# Toplevel.net
KiCad netlist of a schematic drawn in Altium Designer
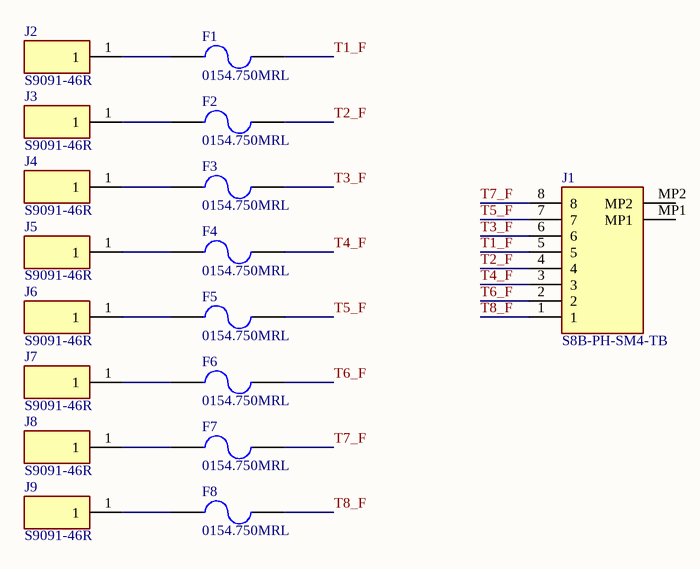
[diagram p0: Toplevel.SchDoc]

(export (version "E")
  (design (tool "Eeschema 10.0.6"))
  (components
    (comp (ref "F1")
      (value "0154.750MRL")
      (footprint "0451Series_LTF")
      (description "FUSE BOARD MNT 750MA 125VAC/VDC")
      (fields
        (field (name "MANUFACTURER") "Littelfuse Inc.")
        (field (name "DIGIKEY PART NUMBER") "F2576CT-ND")
      )
      (libsource (lib "ts_standard_library") (part "Fuse"))
    )
    (comp (ref "F2")
      (value "0154.750MRL")
      (footprint "0451Series_LTF")
      (description "FUSE BOARD MNT 750MA 125VAC/VDC")
      (fields
        (field (name "MANUFACTURER") "Littelfuse Inc.")
        (field (name "DIGIKEY PART NUMBER") "F2576CT-ND")
      )
      (libsource (lib "ts_standard_library") (part "Fuse"))
    )
    (comp (ref "F3")
      (value "0154.750MRL")
      (footprint "0451Series_LTF")
      (description "FUSE BOARD MNT 750MA 125VAC/VDC")
      (fields
        (field (name "MANUFACTURER") "Littelfuse Inc.")
        (field (name "DIGIKEY PART NUMBER") "F2576CT-ND")
      )
      (libsource (lib "ts_standard_library") (part "Fuse"))
    )
    (comp (ref "F4")
      (value "0154.750MRL")
      (footprint "0451Series_LTF")
      (description "FUSE BOARD MNT 750MA 125VAC/VDC")
      (fields
        (field (name "MANUFACTURER") "Littelfuse Inc.")
        (field (name "DIGIKEY PART NUMBER") "F2576CT-ND")
      )
      (libsource (lib "ts_standard_library") (part "Fuse"))
    )
    (comp (ref "F5")
      (value "0154.750MRL")
      (footprint "0451Series_LTF")
      (description "FUSE BOARD MNT 750MA 125VAC/VDC")
      (fields
        (field (name "MANUFACTURER") "Littelfuse Inc.")
        (field (name "DIGIKEY PART NUMBER") "F2576CT-ND")
      )
      (libsource (lib "ts_standard_library") (part "Fuse"))
    )
    (comp (ref "F6")
      (value "0154.750MRL")
      (footprint "0451Series_LTF")
      (description "FUSE BOARD MNT 750MA 125VAC/VDC")
      (fields
        (field (name "MANUFACTURER") "Littelfuse Inc.")
        (field (name "DIGIKEY PART NUMBER") "F2576CT-ND")
      )
      (libsource (lib "ts_standard_library") (part "Fuse"))
    )
    (comp (ref "F7")
      (value "0154.750MRL")
      (footprint "0451Series_LTF")
      (description "FUSE BOARD MNT 750MA 125VAC/VDC")
      (fields
        (field (name "MANUFACTURER") "Littelfuse Inc.")
        (field (name "DIGIKEY PART NUMBER") "F2576CT-ND")
      )
      (libsource (lib "ts_standard_library") (part "Fuse"))
    )
    (comp (ref "F8")
      (value "0154.750MRL")
      (footprint "0451Series_LTF")
      (description "FUSE BOARD MNT 750MA 125VAC/VDC")
      (fields
        (field (name "MANUFACTURER") "Littelfuse Inc.")
        (field (name "DIGIKEY PART NUMBER") "F2576CT-ND")
      )
      (libsource (lib "ts_standard_library") (part "Fuse"))
    )
    (comp (ref "J1")
      (value "S8B-PH-SM4-TB")
      (footprint "SamacSys:S8BPHSM4TB")
      (description "Connector")
      (libsource (lib "*") (part "S8B-PH-SM4-TB"))
    )
    (comp (ref "J2")
      (value "S9091-46R")
      (footprint "SamacSys:S909146R")
      (description "Connector")
      (fields (field (name "MOUSER PART NUMBER") "855-S9091-46R"))
      (libsource (lib "*") (part "S9091-46R"))
    )
    (comp (ref "J3")
      (value "S9091-46R")
      (footprint "SamacSys:S909146R")
      (description "Connector")
      (fields (field (name "MOUSER PART NUMBER") "855-S9091-46R"))
      (libsource (lib "*") (part "S9091-46R"))
    )
    (comp (ref "J4")
      (value "S9091-46R")
      (footprint "SamacSys:S909146R")
      (description "Connector")
      (fields (field (name "MOUSER PART NUMBER") "855-S9091-46R"))
      (libsource (lib "*") (part "S9091-46R"))
    )
    (comp (ref "J5")
      (value "S9091-46R")
      (footprint "SamacSys:S909146R")
      (description "Connector")
      (fields (field (name "MOUSER PART NUMBER") "855-S9091-46R"))
      (libsource (lib "*") (part "S9091-46R"))
    )
    (comp (ref "J6")
      (value "S9091-46R")
      (footprint "SamacSys:S909146R")
      (description "Connector")
      (fields (field (name "MOUSER PART NUMBER") "855-S9091-46R"))
      (libsource (lib "*") (part "S9091-46R"))
    )
    (comp (ref "J7")
      (value "S9091-46R")
      (footprint "SamacSys:S909146R")
      (description "Connector")
      (fields (field (name "MOUSER PART NUMBER") "855-S9091-46R"))
      (libsource (lib "*") (part "S9091-46R"))
    )
    (comp (ref "J8")
      (value "S9091-46R")
      (footprint "SamacSys:S909146R")
      (description "Connector")
      (fields (field (name "MOUSER PART NUMBER") "855-S9091-46R"))
      (libsource (lib "*") (part "S9091-46R"))
    )
    (comp (ref "J9")
      (value "S9091-46R")
      (footprint "SamacSys:S909146R")
      (description "Connector")
      (fields (field (name "MOUSER PART NUMBER") "855-S9091-46R"))
      (libsource (lib "*") (part "S9091-46R"))
    )
  )
  (nets
    (net (code "1") (name "/T1_F") (class "Default")
      (node (ref "F1") (pin "2") (pinfunction "2_2") (pintype "passive"))
      (node (ref "J1") (pin "5") (pinfunction "5_5") (pintype "passive"))
    )
    (net (code "2") (name "/T2_F") (class "Default")
      (node (ref "F2") (pin "2") (pinfunction "2_2") (pintype "passive"))
      (node (ref "J1") (pin "4") (pinfunction "4_4") (pintype "passive"))
    )
    (net (code "3") (name "/T3_F") (class "Default")
      (node (ref "F3") (pin "2") (pinfunction "2_2") (pintype "passive"))
      (node (ref "J1") (pin "6") (pinfunction "6_6") (pintype "passive"))
    )
    (net (code "4") (name "/T4_F") (class "Default")
      (node (ref "F4") (pin "2") (pinfunction "2_2") (pintype "passive"))
      (node (ref "J1") (pin "3") (pinfunction "3_3") (pintype "passive"))
    )
    (net (code "5") (name "/T5_F") (class "Default")
      (node (ref "F5") (pin "2") (pinfunction "2_2") (pintype "passive"))
      (node (ref "J1") (pin "7") (pinfunction "7_7") (pintype "passive"))
    )
    (net (code "6") (name "/T6_F") (class "Default")
      (node (ref "F6") (pin "2") (pinfunction "2_2") (pintype "passive"))
      (node (ref "J1") (pin "2") (pinfunction "2_2") (pintype "passive"))
    )
    (net (code "7") (name "/T7_F") (class "Default")
      (node (ref "F7") (pin "2") (pinfunction "2_2") (pintype "passive"))
      (node (ref "J1") (pin "8") (pinfunction "8_8") (pintype "passive"))
    )
    (net (code "8") (name "/T8_F") (class "Default")
      (node (ref "F8") (pin "2") (pinfunction "2_2") (pintype "passive"))
      (node (ref "J1") (pin "1") (pinfunction "1_1") (pintype "passive"))
    )
    (net (code "9") (name "Net-(F1-Pad1)") (class "Default")
      (node (ref "F1") (pin "1") (pinfunction "1_1") (pintype "passive"))
      (node (ref "J2") (pin "1") (pinfunction "1_1") (pintype "passive"))
    )
    (net (code "10") (name "Net-(F2-Pad1)") (class "Default")
      (node (ref "F2") (pin "1") (pinfunction "1_1") (pintype "passive"))
      (node (ref "J3") (pin "1") (pinfunction "1_1") (pintype "passive"))
    )
    (net (code "11") (name "Net-(F3-Pad1)") (class "Default")
      (node (ref "F3") (pin "1") (pinfunction "1_1") (pintype "passive"))
      (node (ref "J4") (pin "1") (pinfunction "1_1") (pintype "passive"))
    )
    (net (code "12") (name "Net-(F4-Pad1)") (class "Default")
      (node (ref "F4") (pin "1") (pinfunction "1_1") (pintype "passive"))
      (node (ref "J5") (pin "1") (pinfunction "1_1") (pintype "passive"))
    )
    (net (code "13") (name "Net-(F5-Pad1)") (class "Default")
      (node (ref "F5") (pin "1") (pinfunction "1_1") (pintype "passive"))
      (node (ref "J6") (pin "1") (pinfunction "1_1") (pintype "passive"))
    )
    (net (code "14") (name "Net-(F6-Pad1)") (class "Default")
      (node (ref "F6") (pin "1") (pinfunction "1_1") (pintype "passive"))
      (node (ref "J7") (pin "1") (pinfunction "1_1") (pintype "passive"))
    )
    (net (code "15") (name "Net-(F7-Pad1)") (class "Default")
      (node (ref "F7") (pin "1") (pinfunction "1_1") (pintype "passive"))
      (node (ref "J8") (pin "1") (pinfunction "1_1") (pintype "passive"))
    )
    (net (code "16") (name "Net-(F8-Pad1)") (class "Default")
      (node (ref "F8") (pin "1") (pinfunction "1_1") (pintype "passive"))
      (node (ref "J9") (pin "1") (pinfunction "1_1") (pintype "passive"))
    )
    (net (code "17") (name "unconnected-(J1-PadMP1)") (class "Default")
      (node (ref "J1") (pin "MP1") (pinfunction "MP1_MP1") (pintype "passive"))
    )
    (net (code "18") (name "unconnected-(J1-PadMP2)") (class "Default")
      (node (ref "J1") (pin "MP2") (pinfunction "MP2_MP2") (pintype "passive"))
    )
  )
)
